# Sub-A_BPF.net
KiCad netlist of a schematic drawn in Altium Designer
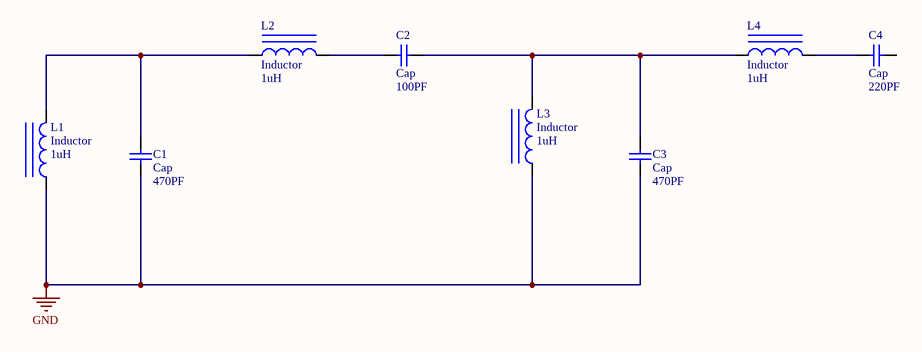
[diagram p0: Sub-A_BPF.SchDoc]

(export (version "E")
  (design (tool "Eeschema 10.0.6"))
  (components
    (comp (ref "C1")
      (value "Cap")
      (footprint "RADIAL-0.1")
      (description "Capacitor")
      (fields
        (field (name "ALTIUM_VALUE") "470PF")
        (field (name "MANUFACTURER PART NUMBER") "K471K15X7RF53L2")
        (field (name "PUBLISHER") "Altium Limited")
      )
      (libsource (lib "ECE295-Capacitors-TH") (part "CAP CER 470PF 50V X7R RADIAL"))
    )
    (comp (ref "C2")
      (value "Cap")
      (footprint "RADIAL-0.1")
      (description "Capacitor")
      (fields
        (field (name "ALTIUM_VALUE") "100PF")
        (field (name "MANUFACTURER PART NUMBER") "K101K15C0GF53L2")
        (field (name "PUBLISHER") "Altium Limited")
      )
      (libsource (lib "ECE295-Capacitors-TH") (part "CAP CER 100PF 50V C0G/NP0 RADIAL"))
    )
    (comp (ref "C3")
      (value "Cap")
      (footprint "RADIAL-0.1")
      (description "Capacitor")
      (fields
        (field (name "ALTIUM_VALUE") "470PF")
        (field (name "MANUFACTURER PART NUMBER") "K471K15X7RF53L2")
        (field (name "PUBLISHER") "Altium Limited")
      )
      (libsource (lib "ECE295-Capacitors-TH") (part "CAP CER 470PF 50V X7R RADIAL"))
    )
    (comp (ref "C4")
      (value "Cap")
      (footprint "RADIAL-0.1")
      (description "Capacitor")
      (fields
        (field (name "ALTIUM_VALUE") "220PF")
        (field (name "MANUFACTURER PART NUMBER") "K221K15X7RF5TH5")
        (field (name "PUBLISHER") "Altium Limited")
      )
      (libsource (lib "ECE295-Capacitors-TH") (part "CAP CER 220PF 50V X7R RADIAL"))
    )
    (comp (ref "L1")
      (value "Inductor")
      (footprint "TORIND-T25")
      (fields (field (name "ALTIUM_VALUE") "1uH") (field (name "PUBLISHER") "Altium Limited"))
      (libsource (lib "ECE295-Other") (part "Toroidal inductor ferrite core"))
    )
    (comp (ref "L2")
      (value "Inductor")
      (footprint "TORIND-T25")
      (fields (field (name "ALTIUM_VALUE") "1uH") (field (name "PUBLISHER") "Altium Limited"))
      (libsource (lib "ECE295-Other") (part "Toroidal inductor ferrite core"))
    )
    (comp (ref "L3")
      (value "Inductor")
      (footprint "TORIND-T25")
      (fields (field (name "ALTIUM_VALUE") "1uH") (field (name "PUBLISHER") "Altium Limited"))
      (libsource (lib "ECE295-Other") (part "Toroidal inductor ferrite core"))
    )
    (comp (ref "L4")
      (value "Inductor")
      (footprint "TORIND-T25")
      (fields (field (name "ALTIUM_VALUE") "1uH") (field (name "PUBLISHER") "Altium Limited"))
      (libsource (lib "ECE295-Other") (part "Toroidal inductor ferrite core"))
    )
  )
  (nets
    (net (code "1") (name "GND") (class "Default")
      (node (ref "C1") (pin "1") (pinfunction "1_1") (pintype "passive"))
      (node (ref "C3") (pin "2") (pinfunction "2_2") (pintype "passive"))
      (node (ref "L1") (pin "1") (pinfunction "1_1") (pintype "passive"))
      (node (ref "L3") (pin "1") (pinfunction "1_1") (pintype "passive"))
    )
    (net (code "2") (name "Net-(C1-Pad2)") (class "Default")
      (node (ref "C1") (pin "2") (pinfunction "2_2") (pintype "passive"))
      (node (ref "L1") (pin "2") (pinfunction "2_2") (pintype "passive"))
      (node (ref "L2") (pin "1") (pinfunction "1_1") (pintype "passive"))
    )
    (net (code "3") (name "Net-(C2-Pad1)") (class "Default")
      (node (ref "C2") (pin "1") (pinfunction "1_1") (pintype "passive"))
      (node (ref "L2") (pin "2") (pinfunction "2_2") (pintype "passive"))
    )
    (net (code "4") (name "Net-(C2-Pad2)") (class "Default")
      (node (ref "C2") (pin "2") (pinfunction "2_2") (pintype "passive"))
      (node (ref "C3") (pin "1") (pinfunction "1_1") (pintype "passive"))
      (node (ref "L3") (pin "2") (pinfunction "2_2") (pintype "passive"))
      (node (ref "L4") (pin "1") (pinfunction "1_1") (pintype "passive"))
    )
    (net (code "5") (name "Net-(C4-Pad1)") (class "Default")
      (node (ref "C4") (pin "1") (pinfunction "1_1") (pintype "passive"))
      (node (ref "L4") (pin "2") (pinfunction "2_2") (pintype "passive"))
    )
    (net (code "6") (name "unconnected-(C4-Pad2)") (class "Default")
      (node (ref "C4") (pin "2") (pinfunction "2_2") (pintype "passive"))
    )
  )
)
